# CH340G.net
KiCad netlist of a schematic drawn in Altium Designer
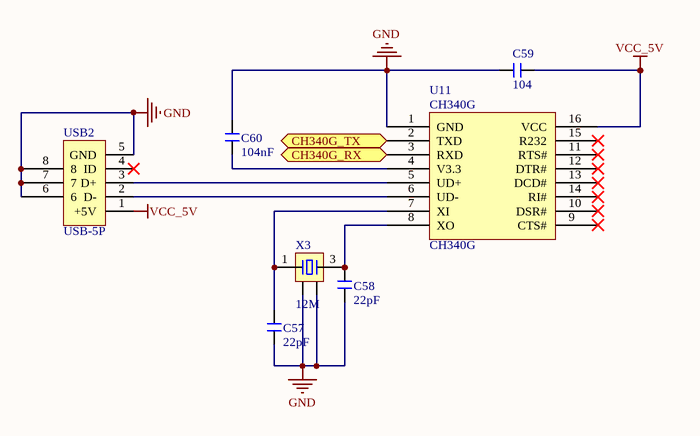
[diagram p0: CH340G.SchDoc]

(export (version "E")
  (design (tool "Eeschema 10.0.6"))
  (components
    (comp (ref "C57")
      (value "22pF")
      (footprint "0603_C")
      (description "无极性贴片电容")
      (libsource (lib "3.1   - 电阻-电容-电感") (part "C"))
    )
    (comp (ref "C58")
      (value "22pF")
      (footprint "0603_C")
      (description "无极性贴片电容")
      (libsource (lib "3.1   - 电阻-电容-电感") (part "C"))
    )
    (comp (ref "C59")
      (value "104")
      (footprint "0603_C")
      (description "无极性贴片电容")
      (libsource (lib "3.1   - 电阻-电容-电感") (part "C"))
    )
    (comp (ref "C60")
      (value "104nF")
      (footprint "0603_C")
      (description "无极性贴片电容")
      (libsource (lib "3.1   - 电阻-电容-电感") (part "C"))
    )
    (comp (ref "U11")
      (value "CH340G")
      (footprint "SOIC-16_150mil")
      (description "USB")
      (libsource (lib "Miscellaneous Devices LC") (part "CH340G"))
    )
    (comp (ref "USB2")
      (value "USB-5P")
      (footprint "micro_usb_47589")
      (description "微型USB母座")
      (fields (field (name "版权归属") "源创客"))
      (libsource (lib "PCB_Project1") (part "USB-5P"))
    )
    (comp (ref "X3")
      (value "12M")
      (footprint "SMD-3225_4P")
      (description "4脚无源晶振")
      (libsource (lib "10.1 - 保险丝-晶振") (part "XTAL-4P"))
    )
  )
  (nets
    (net (code "1") (name "/CH340G_RX") (class "Default")
      (node (ref "U11") (pin "3") (pinfunction "RXD_3") (pintype "passive"))
    )
    (net (code "2") (name "/CH340G_TX") (class "Default")
      (node (ref "U11") (pin "2") (pinfunction "TXD_2") (pintype "passive"))
    )
    (net (code "3") (name "GND") (class "Default")
      (node (ref "C57") (pin "2") (pinfunction "2_2") (pintype "passive"))
      (node (ref "C58") (pin "2") (pinfunction "2_2") (pintype "passive"))
      (node (ref "C59") (pin "1") (pinfunction "1_1") (pintype "passive"))
      (node (ref "C60") (pin "2") (pinfunction "2_2") (pintype "passive"))
      (node (ref "U11") (pin "1") (pinfunction "GND_1") (pintype "passive"))
      (node (ref "USB2") (pin "5") (pinfunction "GND_5") (pintype "passive"))
      (node (ref "USB2") (pin "6") (pinfunction "6_6") (pintype "passive"))
      (node (ref "USB2") (pin "7") (pinfunction "7_7") (pintype "passive"))
      (node (ref "USB2") (pin "8") (pinfunction "8_8") (pintype "passive"))
      (node (ref "X3") (pin "2") (pinfunction "2_2") (pintype "passive"))
      (node (ref "X3") (pin "4") (pinfunction "4_4") (pintype "passive"))
    )
    (net (code "4") (name "Net-(U11-UD+)") (class "Default")
      (node (ref "U11") (pin "5") (pinfunction "UD+_5") (pintype "passive"))
      (node (ref "USB2") (pin "3") (pinfunction "D+_3") (pintype "passive"))
    )
    (net (code "5") (name "Net-(U11-UD-)") (class "Default")
      (node (ref "U11") (pin "6") (pinfunction "UD-_6") (pintype "passive"))
      (node (ref "USB2") (pin "2") (pinfunction "D-_2") (pintype "passive"))
    )
    (net (code "6") (name "Net-(U11-V3.3)") (class "Default")
      (node (ref "C60") (pin "1") (pinfunction "1_1") (pintype "passive"))
      (node (ref "U11") (pin "4") (pinfunction "V3.3_4") (pintype "passive"))
    )
    (net (code "7") (name "Net-(U11-XI)") (class "Default")
      (node (ref "C57") (pin "1") (pinfunction "1_1") (pintype "passive"))
      (node (ref "U11") (pin "7") (pinfunction "XI_7") (pintype "passive"))
      (node (ref "X3") (pin "1") (pinfunction "1_1") (pintype "passive"))
    )
    (net (code "8") (name "Net-(U11-XO)") (class "Default")
      (node (ref "C58") (pin "1") (pinfunction "1_1") (pintype "passive"))
      (node (ref "U11") (pin "8") (pinfunction "XO_8") (pintype "passive"))
      (node (ref "X3") (pin "3") (pinfunction "3_3") (pintype "passive"))
    )
    (net (code "9") (name "VCC_5V") (class "Default")
      (node (ref "C59") (pin "2") (pinfunction "2_2") (pintype "passive"))
      (node (ref "U11") (pin "16") (pinfunction "VCC_16") (pintype "passive"))
      (node (ref "USB2") (pin "1") (pinfunction "+5V_1") (pintype "passive"))
    )
    (net (code "10") (name "unconnected-(U11-CTS#-Pad9)") (class "Default")
      (node (ref "U11") (pin "9") (pinfunction "CTS#_9") (pintype "passive+no_connect"))
    )
    (net (code "11") (name "unconnected-(U11-DCD#-Pad13)") (class "Default")
      (node (ref "U11") (pin "13") (pinfunction "DCD#_13") (pintype "passive+no_connect"))
    )
    (net (code "12") (name "unconnected-(U11-DSR#-Pad10)") (class "Default")
      (node (ref "U11") (pin "10") (pinfunction "DSR#_10") (pintype "passive+no_connect"))
    )
    (net (code "13") (name "unconnected-(U11-DTR#-Pad12)") (class "Default")
      (node (ref "U11") (pin "12") (pinfunction "DTR#_12") (pintype "passive+no_connect"))
    )
    (net (code "14") (name "unconnected-(U11-R232-Pad15)") (class "Default")
      (node (ref "U11") (pin "15") (pinfunction "R232_15") (pintype "passive+no_connect"))
    )
    (net (code "15") (name "unconnected-(U11-RI#-Pad14)") (class "Default")
      (node (ref "U11") (pin "14") (pinfunction "RI#_14") (pintype "passive+no_connect"))
    )
    (net (code "16") (name "unconnected-(U11-RTS#-Pad11)") (class "Default")
      (node (ref "U11") (pin "11") (pinfunction "RTS#_11") (pintype "passive+no_connect"))
    )
    (net (code "17") (name "unconnected-(USB2-ID-Pad4)") (class "Default")
      (node (ref "USB2") (pin "4") (pinfunction "ID_4") (pintype "passive+no_connect"))
    )
  )
)
